# Power_Management.net
KiCad netlist of a schematic drawn in Altium Designer
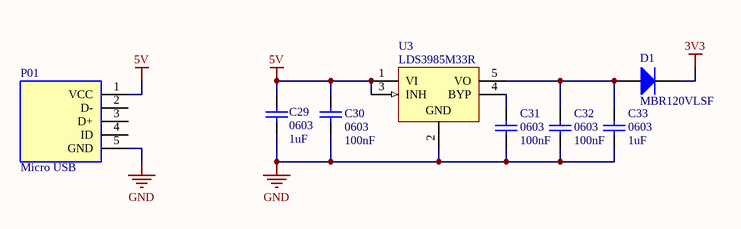
[diagram p0: Power Management.SchDoc]

(export (version "E")
  (design (tool "Eeschema 10.0.6"))
  (components
    (comp (ref "C29")
      (value "0603")
      (footprint "RAD-0.3")
      (description "Capacitor")
      (fields (field (name "ALTIUM_VALUE") "1uF") (field (name "PUBLISHER") "Altium Limited"))
      (libsource (lib "Miscellaneous Devices") (part "Cap"))
    )
    (comp (ref "C30")
      (value "0603")
      (footprint "RAD-0.3")
      (description "Capacitor")
      (fields (field (name "ALTIUM_VALUE") "100nF") (field (name "PUBLISHER") "Altium Limited"))
      (libsource (lib "Miscellaneous Devices") (part "Cap"))
    )
    (comp (ref "C31")
      (value "0603")
      (footprint "RAD-0.3")
      (description "Capacitor")
      (fields (field (name "ALTIUM_VALUE") "100nF") (field (name "PUBLISHER") "Altium Limited"))
      (libsource (lib "Miscellaneous Devices") (part "Cap"))
    )
    (comp (ref "C32")
      (value "0603")
      (footprint "RAD-0.3")
      (description "Capacitor")
      (fields (field (name "ALTIUM_VALUE") "100nF") (field (name "PUBLISHER") "Altium Limited"))
      (libsource (lib "Miscellaneous Devices") (part "Cap"))
    )
    (comp (ref "C33")
      (value "0603")
      (footprint "RAD-0.3")
      (description "Capacitor")
      (fields (field (name "ALTIUM_VALUE") "1uF") (field (name "PUBLISHER") "Altium Limited"))
      (libsource (lib "Miscellaneous Devices") (part "Cap"))
    )
    (comp (ref "D1")
      (value "MBR120VLSF")
      (footprint "SOD375X160X120-2N")
      (description "MBR120VLSF Series 20 V 1 A Surface Mount Schottky Power Rectifier - SOD-123FL")
      (libsource (lib "Schematic_Diode") (part "MBR120VLSF"))
    )
    (comp (ref "P01")
      (value "Micro USB")
      (description "General  Micro USB")
      (libsource (lib "Schematic_Connectors_USB") (part "CONN_MICRO_USB"))
    )
    (comp (ref "U3")
      (value "LDS3985M33R")
      (footprint "SOT23-5L_L")
      (libsource (lib "STMicroelectronics Power Management Linear Regulator") (part "LDS3985M33R"))
    )
  )
  (nets
    (net (code "1") (name "3V3") (class "Default")
      (node (ref "D1") (pin "2") (pinfunction "K_2") (pintype "passive"))
    )
    (net (code "2") (name "5V") (class "Default")
      (node (ref "C29") (pin "2") (pinfunction "2_2") (pintype "passive"))
      (node (ref "C30") (pin "2") (pinfunction "2_2") (pintype "passive"))
      (node (ref "P01") (pin "1") (pinfunction "VCC_1") (pintype "passive"))
      (node (ref "U3") (pin "1") (pinfunction "VI_1") (pintype "power_in"))
      (node (ref "U3") (pin "3") (pinfunction "INH_3") (pintype "input"))
    )
    (net (code "3") (name "GND") (class "Default")
      (node (ref "C29") (pin "1") (pinfunction "1_1") (pintype "passive"))
      (node (ref "C30") (pin "1") (pinfunction "1_1") (pintype "passive"))
      (node (ref "C31") (pin "1") (pinfunction "1_1") (pintype "passive"))
      (node (ref "C32") (pin "1") (pinfunction "1_1") (pintype "passive"))
      (node (ref "C33") (pin "1") (pinfunction "1_1") (pintype "passive"))
      (node (ref "P01") (pin "5") (pinfunction "GND_5") (pintype "passive"))
      (node (ref "U3") (pin "2") (pinfunction "GND_2") (pintype "power_in"))
    )
    (net (code "4") (name "Net-(D1-A)") (class "Default")
      (node (ref "C32") (pin "2") (pinfunction "2_2") (pintype "passive"))
      (node (ref "C33") (pin "2") (pinfunction "2_2") (pintype "passive"))
      (node (ref "D1") (pin "1") (pinfunction "A_1") (pintype "passive"))
      (node (ref "U3") (pin "5") (pinfunction "VO_5") (pintype "power_in"))
    )
    (net (code "5") (name "Net-(U3-BYP)") (class "Default")
      (node (ref "C31") (pin "2") (pinfunction "2_2") (pintype "passive"))
      (node (ref "U3") (pin "4") (pinfunction "BYP_4") (pintype "passive"))
    )
    (net (code "6") (name "unconnected-(P01-D+-Pad3)") (class "Default")
      (node (ref "P01") (pin "3") (pinfunction "D+_3") (pintype "passive"))
    )
    (net (code "7") (name "unconnected-(P01-D--Pad2)") (class "Default")
      (node (ref "P01") (pin "2") (pinfunction "D-_2") (pintype "passive"))
    )
    (net (code "8") (name "unconnected-(P01-ID-Pad4)") (class "Default")
      (node (ref "P01") (pin "4") (pinfunction "ID_4") (pintype "passive"))
    )
  )
)
